# PowerBridge.net
KiCad netlist of a schematic drawn in Altium Designer
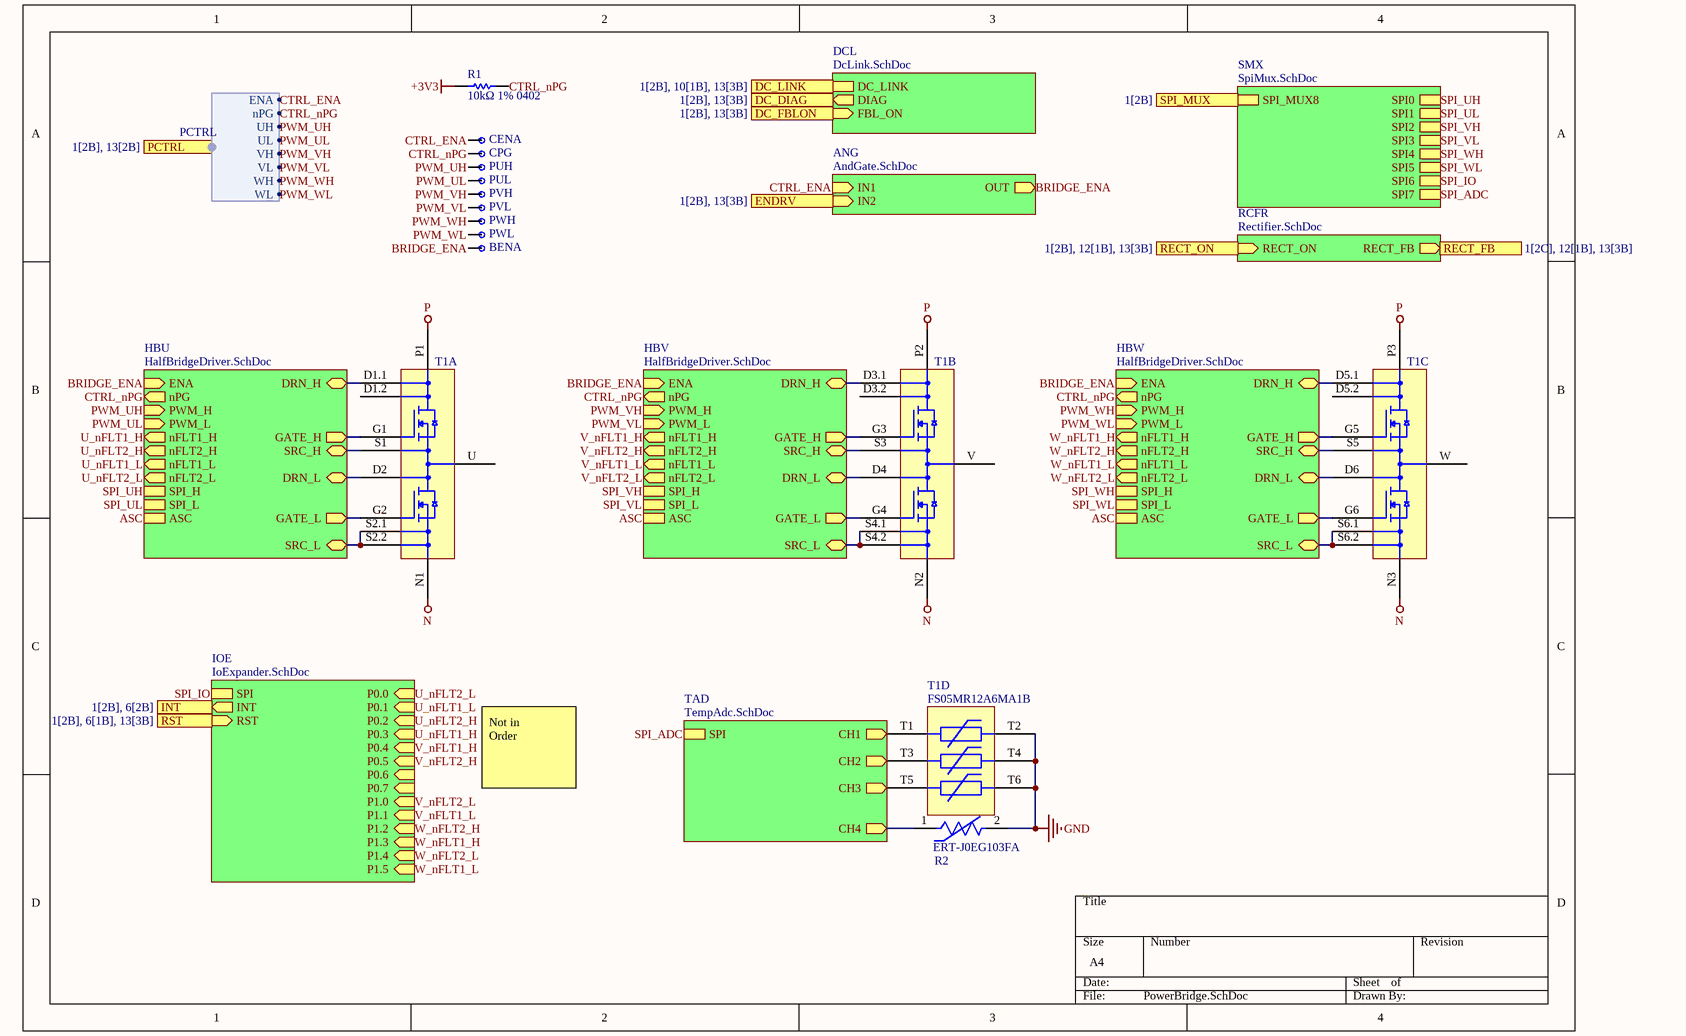
[diagram p0: PowerBridge.SchDoc]

(export (version "E")
  (design (tool "Eeschema 10.0.6"))
  (components
    (comp (ref "BENA")
      (value "Testpoint")
      (footprint "Testpoint-Footprint-1")
      (libsource (lib "Saule S.A") (part "Testpoint"))
    )
    (comp (ref "CENA")
      (value "Testpoint")
      (footprint "Testpoint-Footprint-1")
      (libsource (lib "Saule S.A") (part "Testpoint"))
    )
    (comp (ref "CPG")
      (value "Testpoint")
      (footprint "Testpoint-Footprint-1")
      (libsource (lib "Saule S.A") (part "Testpoint"))
    )
    (comp (ref "PUH")
      (value "Testpoint")
      (footprint "Testpoint-Footprint-1")
      (libsource (lib "Saule S.A") (part "Testpoint"))
    )
    (comp (ref "PUL")
      (value "Testpoint")
      (footprint "Testpoint-Footprint-1")
      (libsource (lib "Saule S.A") (part "Testpoint"))
    )
    (comp (ref "PVH")
      (value "Testpoint")
      (footprint "Testpoint-Footprint-1")
      (libsource (lib "Saule S.A") (part "Testpoint"))
    )
    (comp (ref "PVL")
      (value "Testpoint")
      (footprint "Testpoint-Footprint-1")
      (libsource (lib "Saule S.A") (part "Testpoint"))
    )
    (comp (ref "PWH")
      (value "Testpoint")
      (footprint "Testpoint-Footprint-1")
      (libsource (lib "Saule S.A") (part "Testpoint"))
    )
    (comp (ref "PWL")
      (value "Testpoint")
      (footprint "Testpoint-Footprint-1")
      (libsource (lib "Saule S.A") (part "Testpoint"))
    )
    (comp (ref "R1")
      (value "10kΩ 1% 0402")
      (footprint "0402N")
      (fields (field (name "TOLERANCE") "1"))
      (libsource (lib "MiscPassives") (part "R0402"))
    )
    (comp (ref "R2")
      (value "ERT-J0EG103FA")
      (footprint "FP-ERTJ0-MFG")
      (description "THERMISTOR NTC 10KOHM 3380K 0402")
      (fields (field (name "TOLERANCE") "1%"))
      (libsource (lib "Altium Content Vault") (part "3b148a6ebabc5fb4d708a66c052d352"))
    )
    (comp (ref "T1")
      (value "FS05MR12A6MA1B")
      (footprint "FS05MR12A6MA1B-Footprint-1")
      (description "HybridPACK™ Drive module with CoolSiC™ Automotive MOSFET")
      (libsource (lib "Saule S.A") (part "FS05MR12A6MA1B-Symbol-1"))
    )
  )
  (nets
    (net (code "4") (name "+3V3") (class "Default")
      (node (ref "R1") (pin "1") (pinfunction "1_1") (pintype "passive"))
    )
    (net (code "6") (name "/BRIDGE_ENA") (class "Default")
      (node (ref "BENA") (pin "1") (pinfunction "1_1") (pintype "passive"))
    )
    (net (code "7") (name "/CH1") (class "Default")
      (node (ref "T1") (pin "T1") (pinfunction "PIN_T1") (pintype "passive"))
    )
    (net (code "8") (name "/CH2") (class "Default")
      (node (ref "T1") (pin "T3") (pinfunction "PIN_T3") (pintype "passive"))
    )
    (net (code "9") (name "/CH3") (class "Default")
      (node (ref "T1") (pin "T5") (pinfunction "PIN_T5") (pintype "passive"))
    )
    (net (code "10") (name "/CH4") (class "Default")
      (node (ref "R2") (pin "1") (pinfunction "1_1") (pintype "passive"))
    )
    (net (code "11") (name "/CTRL_ENA") (class "Default")
      (node (ref "CENA") (pin "1") (pinfunction "1_1") (pintype "passive"))
    )
    (net (code "12") (name "/CTRL_nPG") (class "Default")
      (node (ref "CPG") (pin "1") (pinfunction "1_1") (pintype "passive"))
      (node (ref "R1") (pin "2") (pinfunction "2_2") (pintype "passive"))
    )
    (net (code "16") (name "/DRN_H") (class "Default")
      (node (ref "T1") (pin "D1.1") (pinfunction "PIN_D1.1") (pintype "passive"))
    )
    (net (code "17") (name "/DRN_H_1") (class "Default")
      (node (ref "T1") (pin "D3.1") (pinfunction "PIN_D3.1") (pintype "passive"))
    )
    (net (code "18") (name "/DRN_H_2") (class "Default")
      (node (ref "T1") (pin "D5.1") (pinfunction "PIN_D5.1") (pintype "passive"))
    )
    (net (code "19") (name "/DRN_L") (class "Default")
      (node (ref "T1") (pin "D2") (pinfunction "PIN_D2") (pintype "passive"))
    )
    (net (code "20") (name "/DRN_L_1") (class "Default")
      (node (ref "T1") (pin "D4") (pinfunction "PIN_D4") (pintype "passive"))
    )
    (net (code "21") (name "/DRN_L_2") (class "Default")
      (node (ref "T1") (pin "D6") (pinfunction "PIN_D6") (pintype "passive"))
    )
    (net (code "23") (name "/GATE_H") (class "Default")
      (node (ref "T1") (pin "G1") (pinfunction "PIN_G1") (pintype "passive"))
    )
    (net (code "24") (name "/GATE_H_1") (class "Default")
      (node (ref "T1") (pin "G3") (pinfunction "PIN_G3") (pintype "passive"))
    )
    (net (code "25") (name "/GATE_H_2") (class "Default")
      (node (ref "T1") (pin "G5") (pinfunction "PIN_G5") (pintype "passive"))
    )
    (net (code "26") (name "/GATE_L") (class "Default")
      (node (ref "T1") (pin "G2") (pinfunction "PIN_G2") (pintype "passive"))
    )
    (net (code "27") (name "/GATE_L_1") (class "Default")
      (node (ref "T1") (pin "G4") (pinfunction "PIN_G4") (pintype "passive"))
    )
    (net (code "28") (name "/GATE_L_2") (class "Default")
      (node (ref "T1") (pin "G6") (pinfunction "PIN_G6") (pintype "passive"))
    )
    (net (code "32") (name "/PWM_UH") (class "Default")
      (node (ref "PUH") (pin "1") (pinfunction "1_1") (pintype "passive"))
    )
    (net (code "33") (name "/PWM_UL") (class "Default")
      (node (ref "PUL") (pin "1") (pinfunction "1_1") (pintype "passive"))
    )
    (net (code "34") (name "/PWM_VH") (class "Default")
      (node (ref "PVH") (pin "1") (pinfunction "1_1") (pintype "passive"))
    )
    (net (code "35") (name "/PWM_VL") (class "Default")
      (node (ref "PVL") (pin "1") (pinfunction "1_1") (pintype "passive"))
    )
    (net (code "36") (name "/PWM_WH") (class "Default")
      (node (ref "PWH") (pin "1") (pinfunction "1_1") (pintype "passive"))
    )
    (net (code "37") (name "/PWM_WL") (class "Default")
      (node (ref "PWL") (pin "1") (pinfunction "1_1") (pintype "passive"))
    )
    (net (code "50") (name "/SRC_H") (class "Default")
      (node (ref "T1") (pin "S1") (pinfunction "PIN_S1") (pintype "passive"))
    )
    (net (code "51") (name "/SRC_H_1") (class "Default")
      (node (ref "T1") (pin "S3") (pinfunction "PIN_S3") (pintype "passive"))
    )
    (net (code "52") (name "/SRC_H_2") (class "Default")
      (node (ref "T1") (pin "S5") (pinfunction "PIN_S5") (pintype "passive"))
    )
    (net (code "53") (name "/SRC_L") (class "Default")
      (node (ref "T1") (pin "S2.1") (pinfunction "PIN_S2.1") (pintype "passive"))
      (node (ref "T1") (pin "S2.2") (pinfunction "PIN_S2.2") (pintype "passive"))
    )
    (net (code "54") (name "/SRC_L_1") (class "Default")
      (node (ref "T1") (pin "S6.1") (pinfunction "PIN_S6.1") (pintype "passive"))
      (node (ref "T1") (pin "S6.2") (pinfunction "PIN_S6.2") (pintype "passive"))
    )
    (net (code "55") (name "/SRC_L_2") (class "Default")
      (node (ref "T1") (pin "S4.1") (pinfunction "PIN_S4.1") (pintype "passive"))
      (node (ref "T1") (pin "S4.2") (pinfunction "PIN_S4.2") (pintype "passive"))
    )
    (net (code "69") (name "GND") (class "Default")
      (node (ref "R2") (pin "2") (pinfunction "2_2") (pintype "passive"))
      (node (ref "T1") (pin "T2") (pinfunction "PIN_T2") (pintype "passive"))
      (node (ref "T1") (pin "T4") (pinfunction "PIN_T4") (pintype "passive"))
      (node (ref "T1") (pin "T6") (pinfunction "PIN_T6") (pintype "passive"))
    )
    (net (code "70") (name "N") (class "Default")
      (node (ref "T1") (pin "N1") (pinfunction "PIN_N1") (pintype "passive"))
      (node (ref "T1") (pin "N2") (pinfunction "PIN_N2") (pintype "passive"))
      (node (ref "T1") (pin "N3") (pinfunction "PIN_N3") (pintype "passive"))
    )
    (net (code "71") (name "P") (class "Default")
      (node (ref "T1") (pin "P1") (pinfunction "PIN_P1") (pintype "passive"))
      (node (ref "T1") (pin "P2") (pinfunction "PIN_P2") (pintype "passive"))
      (node (ref "T1") (pin "P3") (pinfunction "PIN_P3") (pintype "passive"))
    )
    (net (code "72") (name "unconnected-(T1A-PIN-PadD1.2)") (class "Default")
      (node (ref "T1") (pin "D1.2") (pinfunction "PIN_D1.2") (pintype "passive"))
    )
    (net (code "73") (name "unconnected-(T1A-PIN-PadU)") (class "Default")
      (node (ref "T1") (pin "U") (pinfunction "PIN_U") (pintype "passive"))
    )
    (net (code "74") (name "unconnected-(T1B-PIN-PadD3.2)") (class "Default")
      (node (ref "T1") (pin "D3.2") (pinfunction "PIN_D3.2") (pintype "passive"))
    )
    (net (code "75") (name "unconnected-(T1B-PIN-PadV)") (class "Default")
      (node (ref "T1") (pin "V") (pinfunction "PIN_V") (pintype "passive"))
    )
    (net (code "76") (name "unconnected-(T1C-PIN-PadD5.2)") (class "Default")
      (node (ref "T1") (pin "D5.2") (pinfunction "PIN_D5.2") (pintype "passive"))
    )
    (net (code "77") (name "unconnected-(T1C-PIN-PadW)") (class "Default")
      (node (ref "T1") (pin "W") (pinfunction "PIN_W") (pintype "passive"))
    )
  )
)
